# Security.net
KiCad netlist of a schematic drawn in Altium Designer
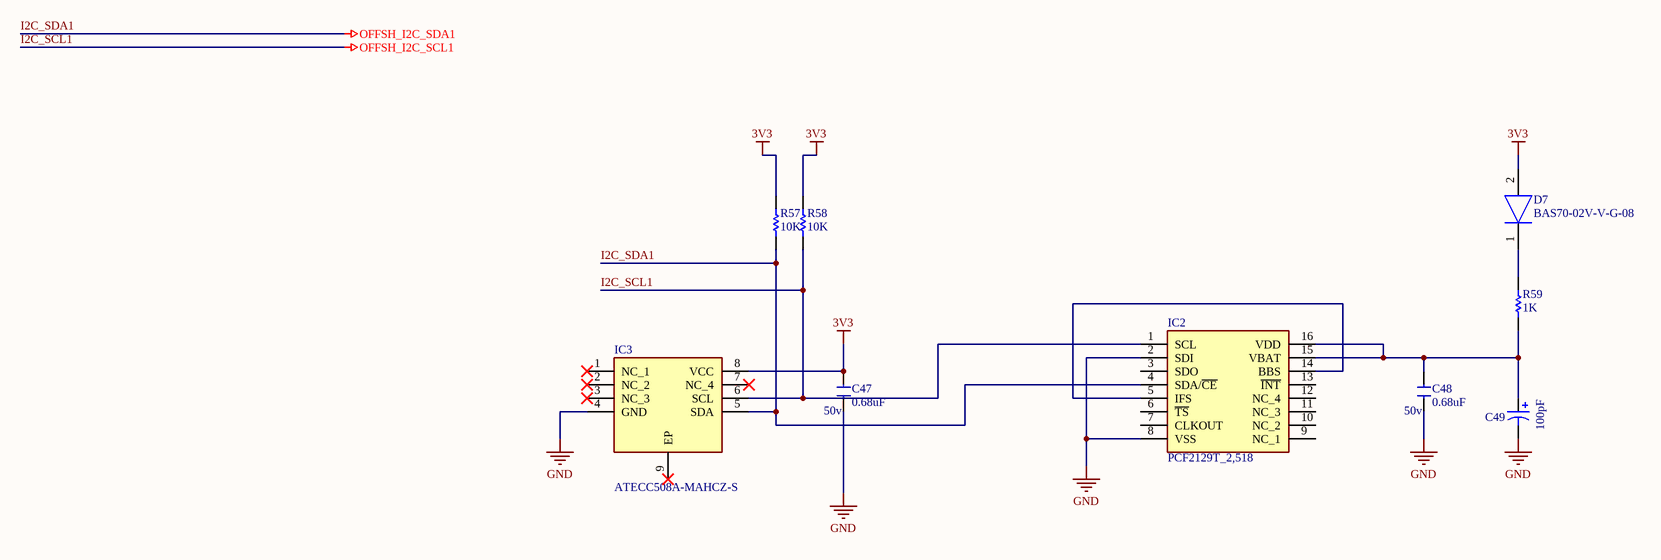
[diagram p0: Security.SchDoc]

(export (version "E")
  (design (tool "Eeschema 10.0.6"))
  (components
    (comp (ref "C47")
      (value "Capacitor SMD")
      (footprint "0603 Capacitor")
      (fields (field (name "ALTIUM_UNNAMED_1") "0.68uF") (field (name "VOLTAGE") "50v"))
      (libsource (lib "SA-C7_Apr09") (part "Capacitor SMD"))
    )
    (comp (ref "C48")
      (value "Capacitor SMD")
      (footprint "0603 Capacitor")
      (fields (field (name "ALTIUM_UNNAMED_1") "0.68uF") (field (name "VOLTAGE") "50v"))
      (libsource (lib "SA-C7_Apr09") (part "Capacitor SMD"))
    )
    (comp (ref "C49")
      (value "100pF")
      (footprint "C0805")
      (description "Polarized Capacitor (Surface Mount)")
      (fields (field (name "Comment") "Cap Pol3") (field (name "PUBLISHER") "Altium Limited"))
      (libsource (lib "Miscellaneous Devices") (part "Cap Pol3"))
    )
    (comp (ref "D7")
      (value "BAS70-02V-V-G-08")
      (footprint "SamacSys:SODFL1608X70N")
      (description "Diode")
      (fields (field (name "MOUSER PART NUMBER") "78-BAS70-02V-V-G-08"))
      (libsource (lib "*") (part "BAS70-02V-V-G-08"))
    )
    (comp (ref "IC2")
      (value "PCF2129T_2,518")
      (footprint "SamacSys:SOIC127P1032X265-16N")
      (description "Integrated Circuit")
      (fields
        (field (name "MANUFACTURER_PART_NUMBER") "PCF2129T/2,518")
        (field (name "MOUSER PART NUMBER") "771-PCF2129T/2,518")
      )
      (libsource (lib "*") (part "PCF2129T_2,518"))
    )
    (comp (ref "IC3")
      (value "ATECC508A-MAHCZ-S")
      (footprint "SamacSys:SON50P300X200X60-9N")
      (description "Integrated Circuit")
      (fields (field (name "MOUSER PART NUMBER") "556-ATECC508AMAHCZS"))
      (libsource (lib "*") (part "ATECC508A-MAHCZ-S"))
    )
    (comp (ref "R57")
      (value "10K")
      (footprint "AXIAL-0.3")
      (description "Resistor")
      (fields (field (name "Comment") "Res1") (field (name "PUBLISHER") "Altium Limited"))
      (libsource (lib "Miscellaneous Devices") (part "Res1"))
    )
    (comp (ref "R58")
      (value "10K")
      (footprint "AXIAL-0.3")
      (description "Resistor")
      (fields (field (name "Comment") "Res1") (field (name "PUBLISHER") "Altium Limited"))
      (libsource (lib "Miscellaneous Devices") (part "Res1"))
    )
    (comp (ref "R59")
      (value "1K")
      (footprint "AXIAL-0.3")
      (description "Resistor")
      (fields (field (name "Comment") "Res1") (field (name "PUBLISHER") "Altium Limited"))
      (libsource (lib "Miscellaneous Devices") (part "Res1"))
    )
  )
  (nets
    (net (code "1") (name "3V3") (class "Default")
      (node (ref "C47") (pin "2") (pintype "passive"))
      (node (ref "D7") (pin "2") (pinfunction "A_2") (pintype "passive"))
      (node (ref "IC3") (pin "8") (pinfunction "VCC_8") (pintype "passive"))
      (node (ref "R57") (pin "1") (pinfunction "1_1") (pintype "passive"))
      (node (ref "R58") (pin "1") (pinfunction "1_1") (pintype "passive"))
    )
    (net (code "2") (name "GND") (class "Default")
      (node (ref "C47") (pin "1") (pintype "passive"))
      (node (ref "C48") (pin "1") (pintype "passive"))
      (node (ref "C49") (pin "2") (pinfunction "2_2") (pintype "passive"))
      (node (ref "IC2") (pin "2") (pinfunction "SDI_2") (pintype "passive"))
      (node (ref "IC2") (pin "8") (pinfunction "VSS_8") (pintype "passive"))
      (node (ref "IC3") (pin "4") (pinfunction "GND_4") (pintype "passive"))
    )
    (net (code "3") (name "Net-(D7-K)") (class "Default")
      (node (ref "D7") (pin "1") (pinfunction "K_1") (pintype "passive"))
      (node (ref "R59") (pin "1") (pinfunction "1_1") (pintype "passive"))
    )
    (net (code "4") (name "Net-(IC2-BBS)") (class "Default")
      (node (ref "IC2") (pin "14") (pinfunction "BBS_14") (pintype "passive"))
      (node (ref "IC2") (pin "5") (pinfunction "IFS_5") (pintype "passive"))
    )
    (net (code "5") (name "Net-(IC2-VBAT)") (class "Default")
      (node (ref "C48") (pin "2") (pintype "passive"))
      (node (ref "C49") (pin "1") (pinfunction "1_1") (pintype "passive"))
      (node (ref "IC2") (pin "15") (pinfunction "VBAT_15") (pintype "passive"))
      (node (ref "IC2") (pin "16") (pinfunction "VDD_16") (pintype "passive"))
      (node (ref "R59") (pin "2") (pinfunction "2_2") (pintype "passive"))
    )
    (net (code "6") (name "OFFSH_I2C_SCL1") (class "Default")
      (node (ref "IC2") (pin "1") (pinfunction "SCL_1") (pintype "passive"))
      (node (ref "IC3") (pin "6") (pinfunction "SCL_6") (pintype "passive"))
      (node (ref "R58") (pin "2") (pinfunction "2_2") (pintype "passive"))
    )
    (net (code "7") (name "OFFSH_I2C_SDA1") (class "Default")
      (node (ref "IC2") (pin "4") (pinfunction "SDA/~{CE}_4") (pintype "passive"))
      (node (ref "IC3") (pin "5") (pinfunction "SDA_5") (pintype "passive"))
      (node (ref "R57") (pin "2") (pinfunction "2_2") (pintype "passive"))
    )
    (net (code "8") (name "unconnected-(IC2-CLKOUT-Pad7)") (class "Default")
      (node (ref "IC2") (pin "7") (pinfunction "CLKOUT_7") (pintype "passive"))
    )
    (net (code "9") (name "unconnected-(IC2-NC_1-Pad9)") (class "Default")
      (node (ref "IC2") (pin "9") (pinfunction "NC_1_9") (pintype "passive"))
    )
    (net (code "10") (name "unconnected-(IC2-NC_2-Pad10)") (class "Default")
      (node (ref "IC2") (pin "10") (pinfunction "NC_2_10") (pintype "passive"))
    )
    (net (code "11") (name "unconnected-(IC2-NC_3-Pad11)") (class "Default")
      (node (ref "IC2") (pin "11") (pinfunction "NC_3_11") (pintype "passive"))
    )
    (net (code "12") (name "unconnected-(IC2-NC_4-Pad12)") (class "Default")
      (node (ref "IC2") (pin "12") (pinfunction "NC_4_12") (pintype "passive"))
    )
    (net (code "13") (name "unconnected-(IC2-SDO-Pad3)") (class "Default")
      (node (ref "IC2") (pin "3") (pinfunction "SDO_3") (pintype "passive"))
    )
    (net (code "14") (name "unconnected-(IC2-~{INT}-Pad13)") (class "Default")
      (node (ref "IC2") (pin "13") (pinfunction "~{INT}_13") (pintype "passive"))
    )
    (net (code "15") (name "unconnected-(IC2-~{TS}-Pad6)") (class "Default")
      (node (ref "IC2") (pin "6") (pinfunction "~{TS}_6") (pintype "passive"))
    )
    (net (code "16") (name "unconnected-(IC3-EP-Pad9)") (class "Default")
      (node (ref "IC3") (pin "9") (pinfunction "EP_9") (pintype "passive+no_connect"))
    )
    (net (code "17") (name "unconnected-(IC3-NC_1-Pad1)") (class "Default")
      (node (ref "IC3") (pin "1") (pinfunction "NC_1_1") (pintype "passive+no_connect"))
    )
    (net (code "18") (name "unconnected-(IC3-NC_2-Pad2)") (class "Default")
      (node (ref "IC3") (pin "2") (pinfunction "NC_2_2") (pintype "passive+no_connect"))
    )
    (net (code "19") (name "unconnected-(IC3-NC_3-Pad3)") (class "Default")
      (node (ref "IC3") (pin "3") (pinfunction "NC_3_3") (pintype "passive+no_connect"))
    )
    (net (code "20") (name "unconnected-(IC3-NC_4-Pad7)") (class "Default")
      (node (ref "IC3") (pin "7") (pinfunction "NC_4_7") (pintype "passive+no_connect"))
    )
  )
)
